# nceubadge.net
KiCad netlist of a schematic drawn in EAGLE
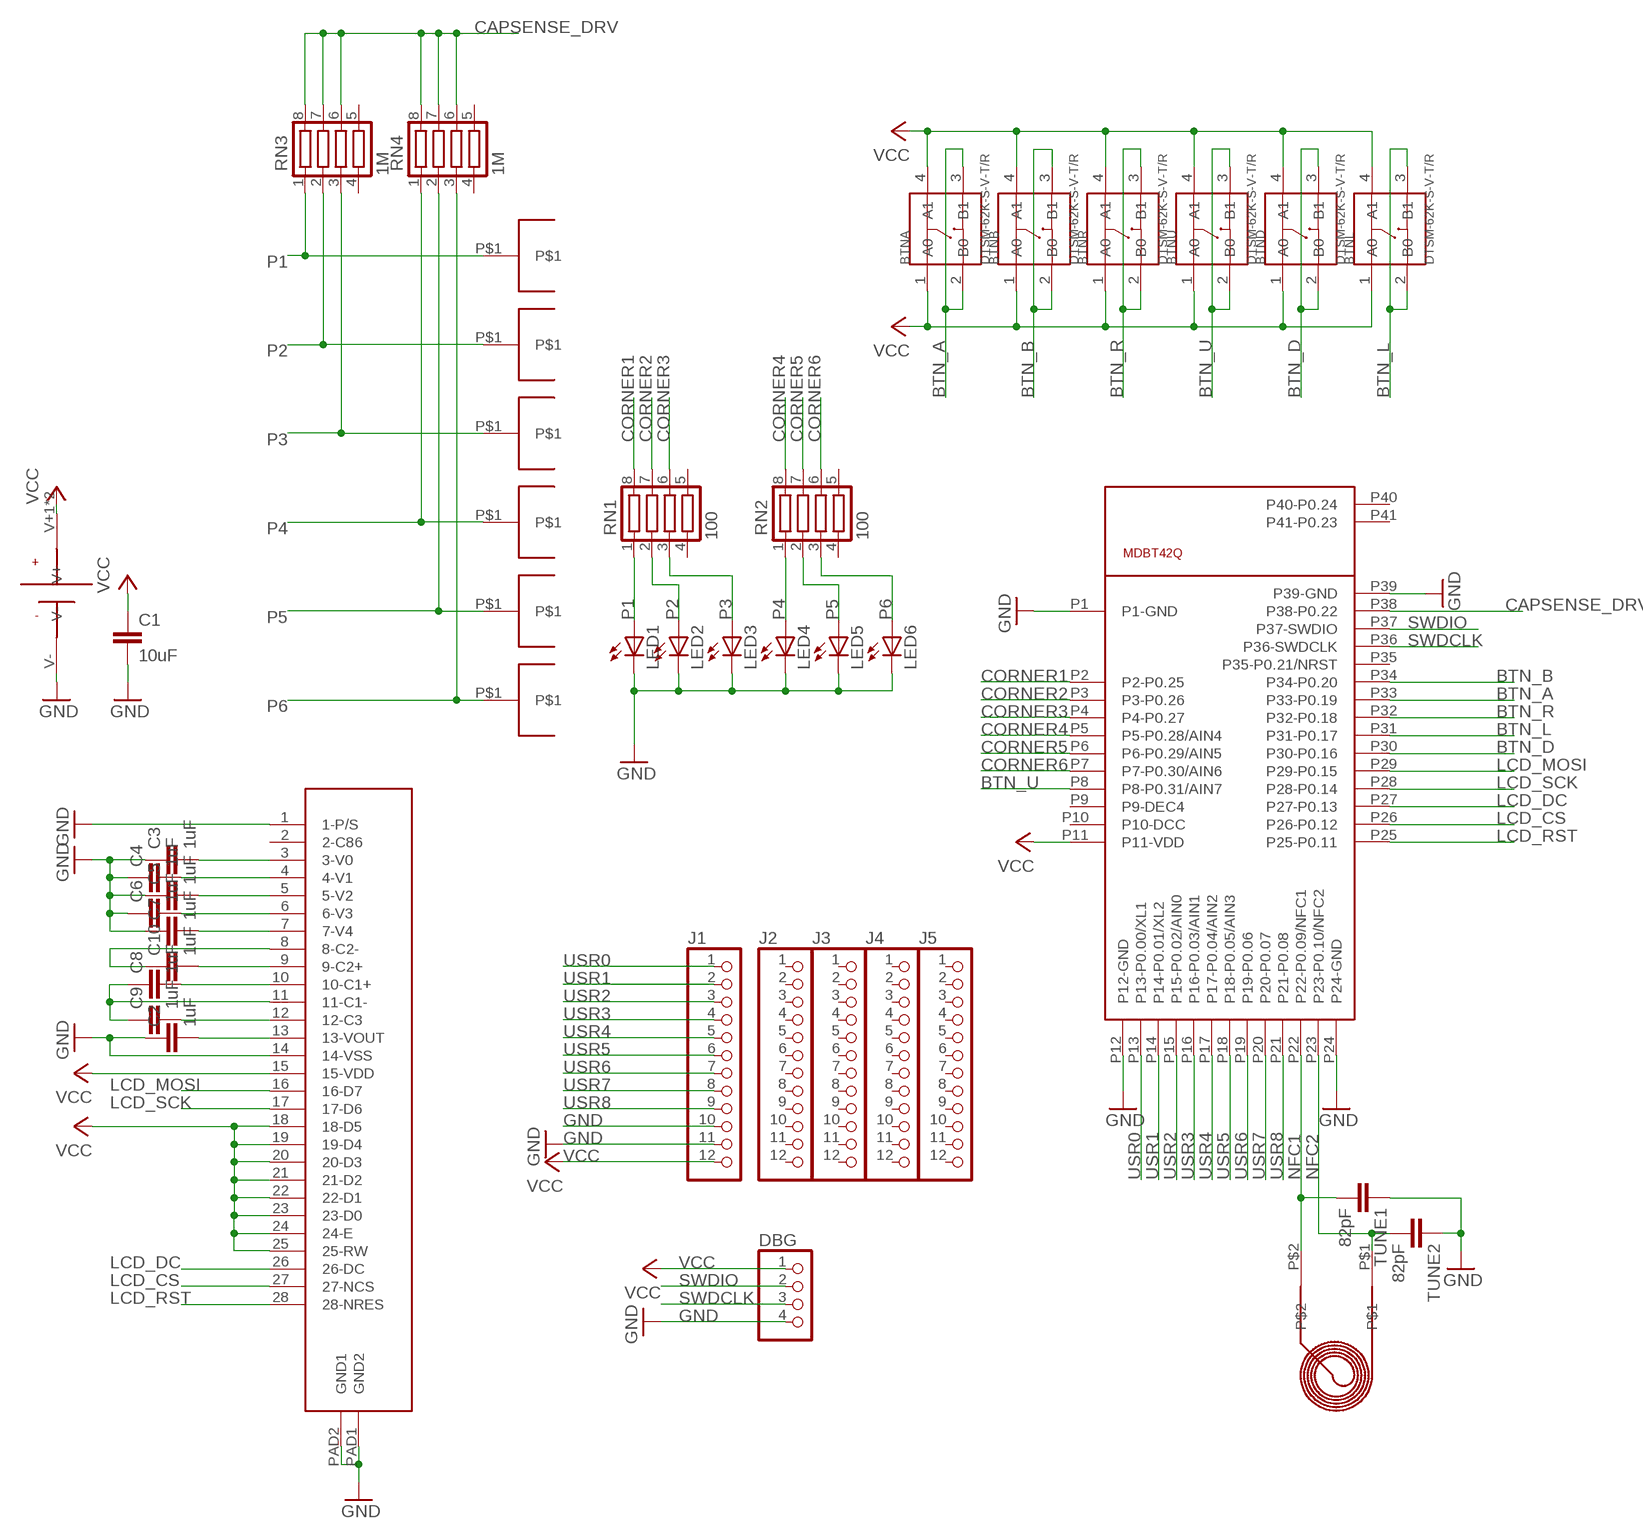
[diagram p0: schematic, sheet 1]

(export (version "E")
  (design (tool "Eeschema 10.0.6"))
  (components
    (comp (ref "BTNA")
      (value "DTSM-62K-S-V-T/R")
      (footprint "eagle-import:SW4-SMD-6.0X6.0X5.0MM")
      (libsource (lib "eagle-import") (part "SMD-SWITCH-TACTILE-SPST-NO(4P-D6.0MM)"))
    )
    (comp (ref "BTNB")
      (value "DTSM-62K-S-V-T/R")
      (footprint "eagle-import:SW4-SMD-6.0X6.0X5.0MM")
      (libsource (lib "eagle-import") (part "SMD-SWITCH-TACTILE-SPST-NO(4P-D6.0MM)"))
    )
    (comp (ref "BTND")
      (value "DTSM-62K-S-V-T/R")
      (footprint "eagle-import:SW4-SMD-6.0X6.0X5.0MM")
      (libsource (lib "eagle-import") (part "SMD-SWITCH-TACTILE-SPST-NO(4P-D6.0MM)"))
    )
    (comp (ref "BTNL")
      (value "DTSM-62K-S-V-T/R")
      (footprint "eagle-import:SW4-SMD-6.0X6.0X5.0MM")
      (libsource (lib "eagle-import") (part "SMD-SWITCH-TACTILE-SPST-NO(4P-D6.0MM)"))
    )
    (comp (ref "BTNR")
      (value "DTSM-62K-S-V-T/R")
      (footprint "eagle-import:SW4-SMD-6.0X6.0X5.0MM")
      (libsource (lib "eagle-import") (part "SMD-SWITCH-TACTILE-SPST-NO(4P-D6.0MM)"))
    )
    (comp (ref "BTNU")
      (value "DTSM-62K-S-V-T/R")
      (footprint "eagle-import:SW4-SMD-6.0X6.0X5.0MM")
      (libsource (lib "eagle-import") (part "SMD-SWITCH-TACTILE-SPST-NO(4P-D6.0MM)"))
    )
    (comp (ref "C1")
      (value "10uF")
      (footprint "eagle-import:C0805K")
      (libsource (lib "eagle-import") (part "C-EUC0805K"))
    )
    (comp (ref "C2")
      (value "1uF")
      (footprint "eagle-import:C0603")
      (libsource (lib "eagle-import") (part "C-EUC0603"))
    )
    (comp (ref "C3")
      (value "1uF")
      (footprint "eagle-import:C0603")
      (libsource (lib "eagle-import") (part "C-EUC0603"))
    )
    (comp (ref "C4")
      (value "1uF")
      (footprint "eagle-import:C0603")
      (libsource (lib "eagle-import") (part "C-EUC0603"))
    )
    (comp (ref "C5")
      (value "1uF")
      (footprint "eagle-import:C0603")
      (libsource (lib "eagle-import") (part "C-EUC0603"))
    )
    (comp (ref "C6")
      (value "1uF")
      (footprint "eagle-import:C0603")
      (libsource (lib "eagle-import") (part "C-EUC0603"))
    )
    (comp (ref "C7")
      (value "1uF")
      (footprint "eagle-import:C0603")
      (libsource (lib "eagle-import") (part "C-EUC0603"))
    )
    (comp (ref "C8")
      (value "1uF")
      (footprint "eagle-import:C0603")
      (libsource (lib "eagle-import") (part "C-EUC0603"))
    )
    (comp (ref "C9")
      (value "1uF")
      (footprint "eagle-import:C0603")
      (libsource (lib "eagle-import") (part "C-EUC0603"))
    )
    (comp (ref "C10")
      (value "1uF")
      (footprint "eagle-import:C0603")
      (libsource (lib "eagle-import") (part "C-EUC0603"))
    )
    (comp (ref "DBG")
      (value "PINHD-1X4")
      (footprint "eagle-import:1X04")
      (libsource (lib "eagle-import") (part "PINHD-1X4"))
    )
    (comp (ref "J1")
      (value "PINHD-1X12_2.54-S")
      (footprint "eagle-import:1X12-S")
      (libsource (lib "eagle-import") (part "PINHD-1X12_2.54-S"))
    )
    (comp (ref "J2")
      (value "PINHD-1X12_2.54-S")
      (footprint "eagle-import:1X12-S")
      (libsource (lib "eagle-import") (part "PINHD-1X12_2.54-S"))
    )
    (comp (ref "J3")
      (value "PINHD-1X12_2.54-S")
      (footprint "eagle-import:1X12-S")
      (libsource (lib "eagle-import") (part "PINHD-1X12_2.54-S"))
    )
    (comp (ref "J4")
      (value "PINHD-1X12_2.54-S")
      (footprint "eagle-import:1X12-S")
      (libsource (lib "eagle-import") (part "PINHD-1X12_2.54-S"))
    )
    (comp (ref "J5")
      (value "PINHD-1X12_2.54-S")
      (footprint "eagle-import:1X12-S")
      (libsource (lib "eagle-import") (part "PINHD-1X12_2.54-S"))
    )
    (comp (ref "J8")
      (value "KEYSTONE-3003")
      (footprint "eagle-import:KEYSTONE-3003")
      (libsource (lib "eagle-import") (part "KEYSTONE-3003"))
    )
    (comp (ref "LCD")
      (value "MCCOG128064B12W")
      (footprint "eagle-import:MCOG128064B12W-SPR")
      (libsource (lib "eagle-import") (part "MCCOG128064B12W"))
    )
    (comp (ref "LED1")
      (value "LED5MM")
      (footprint "eagle-import:LED5MM")
      (libsource (lib "eagle-import") (part "LED5MM"))
    )
    (comp (ref "LED2")
      (value "LED5MM")
      (footprint "eagle-import:LED5MM")
      (libsource (lib "eagle-import") (part "LED5MM"))
    )
    (comp (ref "LED3")
      (value "LED5MM")
      (footprint "eagle-import:LED5MM")
      (libsource (lib "eagle-import") (part "LED5MM"))
    )
    (comp (ref "LED4")
      (value "LED5MM")
      (footprint "eagle-import:LED5MM")
      (libsource (lib "eagle-import") (part "LED5MM"))
    )
    (comp (ref "LED5")
      (value "LED5MM")
      (footprint "eagle-import:LED5MM")
      (libsource (lib "eagle-import") (part "LED5MM"))
    )
    (comp (ref "LED6")
      (value "LED5MM")
      (footprint "eagle-import:LED5MM")
      (libsource (lib "eagle-import") (part "LED5MM"))
    )
    (comp (ref "RN1")
      (value "100")
      (footprint "eagle-import:CTS742C083")
      (libsource (lib "eagle-import") (part "CTS742C083"))
    )
    (comp (ref "RN2")
      (value "100")
      (footprint "eagle-import:CTS742C083")
      (libsource (lib "eagle-import") (part "CTS742C083"))
    )
    (comp (ref "RN3")
      (value "1M")
      (footprint "eagle-import:CTS742C083")
      (libsource (lib "eagle-import") (part "CTS742C083"))
    )
    (comp (ref "RN4")
      (value "1M")
      (footprint "eagle-import:CTS742C083")
      (libsource (lib "eagle-import") (part "CTS742C083"))
    )
    (comp (ref "TUNE1")
      (value "82pF")
      (footprint "eagle-import:C0603")
      (libsource (lib "eagle-import") (part "C-EUC0603"))
    )
    (comp (ref "TUNE2")
      (value "82pF")
      (footprint "eagle-import:C0603")
      (libsource (lib "eagle-import") (part "C-EUC0603"))
    )
    (comp (ref "U$2")
      (value "BANANAPLUG")
      (footprint "eagle-import:BANANAPLUG")
      (libsource (lib "eagle-import") (part "BANANAPLUG"))
    )
    (comp (ref "U$3")
      (value "BANANAPLUG")
      (footprint "eagle-import:BANANAPLUG")
      (libsource (lib "eagle-import") (part "BANANAPLUG"))
    )
    (comp (ref "U$4")
      (value "BANANAPLUG")
      (footprint "eagle-import:BANANAPLUG")
      (libsource (lib "eagle-import") (part "BANANAPLUG"))
    )
    (comp (ref "U$5")
      (value "BANANAPLUG")
      (footprint "eagle-import:BANANAPLUG")
      (libsource (lib "eagle-import") (part "BANANAPLUG"))
    )
    (comp (ref "U$6")
      (value "BANANAPLUG")
      (footprint "eagle-import:BANANAPLUG")
      (libsource (lib "eagle-import") (part "BANANAPLUG"))
    )
    (comp (ref "U$7")
      (value "BANANAPLUG")
      (footprint "eagle-import:BANANAPLUG")
      (libsource (lib "eagle-import") (part "BANANAPLUG"))
    )
    (comp (ref "U$8")
      (value "NFC")
      (footprint "eagle-import:NFC")
      (libsource (lib "eagle-import") (part "NFC"))
    )
    (comp (ref "U1")
      (value "MDBT42Q")
      (footprint "eagle-import:MDBT40")
      (libsource (lib "eagle-import") (part "MDBT42Q"))
    )
  )
  (nets
    (net (code "1") (name "/BTN_A") (class "Default")
      (node (ref "BTNA") (pin "2") (pinfunction "B0_2") (pintype "bidirectional"))
      (node (ref "BTNA") (pin "3") (pinfunction "B1_3") (pintype "bidirectional"))
      (node (ref "U1") (pin "P33") (pinfunction "P33-P0.19_P33") (pintype "bidirectional"))
    )
    (net (code "2") (name "/BTN_B") (class "Default")
      (node (ref "BTNB") (pin "2") (pinfunction "B0_2") (pintype "bidirectional"))
      (node (ref "BTNB") (pin "3") (pinfunction "B1_3") (pintype "bidirectional"))
      (node (ref "U1") (pin "P34") (pinfunction "P34-P0.20_P34") (pintype "bidirectional"))
    )
    (net (code "3") (name "/BTN_D") (class "Default")
      (node (ref "BTND") (pin "2") (pinfunction "B0_2") (pintype "bidirectional"))
      (node (ref "BTND") (pin "3") (pinfunction "B1_3") (pintype "bidirectional"))
      (node (ref "U1") (pin "P30") (pinfunction "P30-P0.16_P30") (pintype "bidirectional"))
    )
    (net (code "4") (name "/BTN_L") (class "Default")
      (node (ref "BTNL") (pin "2") (pinfunction "B0_2") (pintype "bidirectional"))
      (node (ref "BTNL") (pin "3") (pinfunction "B1_3") (pintype "bidirectional"))
      (node (ref "U1") (pin "P31") (pinfunction "P31-P0.17_P31") (pintype "bidirectional"))
    )
    (net (code "5") (name "/BTN_R") (class "Default")
      (node (ref "BTNR") (pin "2") (pinfunction "B0_2") (pintype "bidirectional"))
      (node (ref "BTNR") (pin "3") (pinfunction "B1_3") (pintype "bidirectional"))
      (node (ref "U1") (pin "P32") (pinfunction "P32-P0.18_P32") (pintype "bidirectional"))
    )
    (net (code "6") (name "/BTN_U") (class "Default")
      (node (ref "BTNU") (pin "2") (pinfunction "B0_2") (pintype "bidirectional"))
      (node (ref "BTNU") (pin "3") (pinfunction "B1_3") (pintype "bidirectional"))
      (node (ref "U1") (pin "P8") (pinfunction "P8-P0.31/AIN7_P8") (pintype "bidirectional"))
    )
    (net (code "7") (name "/CAPSENSE_DRV") (class "Default")
      (node (ref "RN3") (pin "6") (pinfunction "6_6") (pintype "passive"))
      (node (ref "RN3") (pin "7") (pinfunction "7_7") (pintype "passive"))
      (node (ref "RN3") (pin "8") (pinfunction "8_8") (pintype "passive"))
      (node (ref "RN4") (pin "6") (pinfunction "6_6") (pintype "passive"))
      (node (ref "RN4") (pin "7") (pinfunction "7_7") (pintype "passive"))
      (node (ref "RN4") (pin "8") (pinfunction "8_8") (pintype "passive"))
      (node (ref "U1") (pin "P38") (pinfunction "P38-P0.22_P38") (pintype "bidirectional"))
    )
    (net (code "8") (name "/CORNER1") (class "Default")
      (node (ref "RN1") (pin "8") (pinfunction "8_8") (pintype "passive"))
      (node (ref "U1") (pin "P2") (pinfunction "P2-P0.25_P2") (pintype "bidirectional"))
    )
    (net (code "9") (name "/CORNER2") (class "Default")
      (node (ref "RN1") (pin "7") (pinfunction "7_7") (pintype "passive"))
      (node (ref "U1") (pin "P3") (pinfunction "P3-P0.26_P3") (pintype "bidirectional"))
    )
    (net (code "10") (name "/CORNER3") (class "Default")
      (node (ref "RN1") (pin "6") (pinfunction "6_6") (pintype "passive"))
      (node (ref "U1") (pin "P4") (pinfunction "P4-P0.27_P4") (pintype "bidirectional"))
    )
    (net (code "11") (name "/CORNER4") (class "Default")
      (node (ref "RN2") (pin "8") (pinfunction "8_8") (pintype "passive"))
      (node (ref "U1") (pin "P5") (pinfunction "P5-P0.28/AIN4_P5") (pintype "bidirectional"))
    )
    (net (code "12") (name "/CORNER5") (class "Default")
      (node (ref "RN2") (pin "7") (pinfunction "7_7") (pintype "passive"))
      (node (ref "U1") (pin "P6") (pinfunction "P6-P0.29/AIN5_P6") (pintype "bidirectional"))
    )
    (net (code "13") (name "/CORNER6") (class "Default")
      (node (ref "RN2") (pin "6") (pinfunction "6_6") (pintype "passive"))
      (node (ref "U1") (pin "P7") (pinfunction "P7-P0.30/AIN6_P7") (pintype "bidirectional"))
    )
    (net (code "14") (name "/LCD_CS") (class "Default")
      (node (ref "LCD") (pin "27") (pinfunction "27-NCS_27") (pintype "bidirectional"))
      (node (ref "U1") (pin "P26") (pinfunction "P26-P0.12_P26") (pintype "bidirectional"))
    )
    (net (code "15") (name "/LCD_DC") (class "Default")
      (node (ref "LCD") (pin "26") (pinfunction "26-DC_26") (pintype "bidirectional"))
      (node (ref "U1") (pin "P27") (pinfunction "P27-P0.13_P27") (pintype "bidirectional"))
    )
    (net (code "16") (name "/LCD_MOSI") (class "Default")
      (node (ref "LCD") (pin "16") (pinfunction "16-D7_16") (pintype "bidirectional"))
      (node (ref "U1") (pin "P29") (pinfunction "P29-P0.15_P29") (pintype "bidirectional"))
    )
    (net (code "17") (name "/LCD_RST") (class "Default")
      (node (ref "LCD") (pin "28") (pinfunction "28-NRES_28") (pintype "bidirectional"))
      (node (ref "U1") (pin "P25") (pinfunction "P25-P0.11_P25") (pintype "bidirectional"))
    )
    (net (code "18") (name "/LCD_SCK") (class "Default")
      (node (ref "LCD") (pin "17") (pinfunction "17-D6_17") (pintype "bidirectional"))
      (node (ref "U1") (pin "P28") (pinfunction "P28-P0.14_P28") (pintype "bidirectional"))
    )
    (net (code "19") (name "/NFC1") (class "Default")
      (node (ref "TUNE1") (pin "2") (pinfunction "2_2") (pintype "passive"))
      (node (ref "U$8") (pin "P$2") (pinfunction "P$2_P$2") (pintype "bidirectional"))
      (node (ref "U1") (pin "P22") (pinfunction "P22-P0.09/NFC1_P22") (pintype "bidirectional"))
    )
    (net (code "20") (name "/NFC2") (class "Default")
      (node (ref "TUNE2") (pin "2") (pinfunction "2_2") (pintype "passive"))
      (node (ref "U$8") (pin "P$1") (pinfunction "P$1_P$1") (pintype "bidirectional"))
      (node (ref "U1") (pin "P23") (pinfunction "P23-P0.10/NFC2_P23") (pintype "bidirectional"))
    )
    (net (code "21") (name "/P1") (class "Default")
      (node (ref "LED1") (pin "A") (pinfunction "A_A") (pintype "passive"))
      (node (ref "RN1") (pin "1") (pinfunction "1_1") (pintype "passive"))
      (node (ref "RN3") (pin "1") (pinfunction "1_1") (pintype "passive"))
      (node (ref "U$6") (pin "P$1") (pinfunction "P$1_P$1") (pintype "bidirectional"))
    )
    (net (code "22") (name "/P2") (class "Default")
      (node (ref "LED2") (pin "A") (pinfunction "A_A") (pintype "passive"))
      (node (ref "RN1") (pin "2") (pinfunction "2_2") (pintype "passive"))
      (node (ref "RN3") (pin "2") (pinfunction "2_2") (pintype "passive"))
      (node (ref "U$7") (pin "P$1") (pinfunction "P$1_P$1") (pintype "bidirectional"))
    )
    (net (code "23") (name "/P3") (class "Default")
      (node (ref "LED3") (pin "A") (pinfunction "A_A") (pintype "passive"))
      (node (ref "RN1") (pin "3") (pinfunction "3_3") (pintype "passive"))
      (node (ref "RN3") (pin "3") (pinfunction "3_3") (pintype "passive"))
      (node (ref "U$5") (pin "P$1") (pinfunction "P$1_P$1") (pintype "bidirectional"))
    )
    (net (code "24") (name "/P4") (class "Default")
      (node (ref "LED4") (pin "A") (pinfunction "A_A") (pintype "passive"))
      (node (ref "RN2") (pin "1") (pinfunction "1_1") (pintype "passive"))
      (node (ref "RN4") (pin "1") (pinfunction "1_1") (pintype "passive"))
      (node (ref "U$4") (pin "P$1") (pinfunction "P$1_P$1") (pintype "bidirectional"))
    )
    (net (code "25") (name "/P5") (class "Default")
      (node (ref "LED5") (pin "A") (pinfunction "A_A") (pintype "passive"))
      (node (ref "RN2") (pin "2") (pinfunction "2_2") (pintype "passive"))
      (node (ref "RN4") (pin "2") (pinfunction "2_2") (pintype "passive"))
      (node (ref "U$3") (pin "P$1") (pinfunction "P$1_P$1") (pintype "bidirectional"))
    )
    (net (code "26") (name "/P6") (class "Default")
      (node (ref "LED6") (pin "A") (pinfunction "A_A") (pintype "passive"))
      (node (ref "RN2") (pin "3") (pinfunction "3_3") (pintype "passive"))
      (node (ref "RN4") (pin "3") (pinfunction "3_3") (pintype "passive"))
      (node (ref "U$2") (pin "P$1") (pinfunction "P$1_P$1") (pintype "bidirectional"))
    )
    (net (code "27") (name "/SWDCLK") (class "Default")
      (node (ref "DBG") (pin "3") (pinfunction "3_3") (pintype "passive"))
      (node (ref "U1") (pin "P36") (pinfunction "P36-SWDCLK_P36") (pintype "bidirectional"))
    )
    (net (code "28") (name "/SWDIO") (class "Default")
      (node (ref "DBG") (pin "2") (pinfunction "2_2") (pintype "passive"))
      (node (ref "U1") (pin "P37") (pinfunction "P37-SWDIO_P37") (pintype "bidirectional"))
    )
    (net (code "29") (name "/USR0") (class "Default")
      (node (ref "J1") (pin "1") (pinfunction "1_1") (pintype "passive"))
      (node (ref "U1") (pin "P13") (pinfunction "P13-P0.00/XL1_P13") (pintype "bidirectional"))
    )
    (net (code "30") (name "/USR1") (class "Default")
      (node (ref "J1") (pin "2") (pinfunction "2_2") (pintype "passive"))
      (node (ref "U1") (pin "P14") (pinfunction "P14-P0.01/XL2_P14") (pintype "bidirectional"))
    )
    (net (code "31") (name "/USR2") (class "Default")
      (node (ref "J1") (pin "3") (pinfunction "3_3") (pintype "passive"))
      (node (ref "U1") (pin "P15") (pinfunction "P15-P0.02/AIN0_P15") (pintype "bidirectional"))
    )
    (net (code "32") (name "/USR3") (class "Default")
      (node (ref "J1") (pin "4") (pinfunction "4_4") (pintype "passive"))
      (node (ref "U1") (pin "P16") (pinfunction "P16-P0.03/AIN1_P16") (pintype "bidirectional"))
    )
    (net (code "33") (name "/USR4") (class "Default")
      (node (ref "J1") (pin "5") (pinfunction "5_5") (pintype "passive"))
      (node (ref "U1") (pin "P17") (pinfunction "P17-P0.04/AIN2_P17") (pintype "bidirectional"))
    )
    (net (code "34") (name "/USR5") (class "Default")
      (node (ref "J1") (pin "6") (pinfunction "6_6") (pintype "passive"))
      (node (ref "U1") (pin "P18") (pinfunction "P18-P0.05/AIN3_P18") (pintype "bidirectional"))
    )
    (net (code "35") (name "/USR6") (class "Default")
      (node (ref "J1") (pin "7") (pinfunction "7_7") (pintype "passive"))
      (node (ref "U1") (pin "P19") (pinfunction "P19-P0.06_P19") (pintype "bidirectional"))
    )
    (net (code "36") (name "/USR7") (class "Default")
      (node (ref "J1") (pin "8") (pinfunction "8_8") (pintype "passive"))
      (node (ref "U1") (pin "P20") (pinfunction "P20-P0.07_P20") (pintype "bidirectional"))
    )
    (net (code "37") (name "/USR8") (class "Default")
      (node (ref "J1") (pin "9") (pinfunction "9_9") (pintype "passive"))
      (node (ref "U1") (pin "P21") (pinfunction "P21-P0.08_P21") (pintype "bidirectional"))
    )
    (net (code "38") (name "GND") (class "Default")
      (node (ref "C1") (pin "2") (pinfunction "2_2") (pintype "passive"))
      (node (ref "C2") (pin "1") (pinfunction "1_1") (pintype "passive"))
      (node (ref "C3") (pin "1") (pinfunction "1_1") (pintype "passive"))
      (node (ref "C4") (pin "1") (pinfunction "1_1") (pintype "passive"))
      (node (ref "C5") (pin "1") (pinfunction "1_1") (pintype "passive"))
      (node (ref "C6") (pin "1") (pinfunction "1_1") (pintype "passive"))
      (node (ref "C7") (pin "1") (pinfunction "1_1") (pintype "passive"))
      (node (ref "DBG") (pin "4") (pinfunction "4_4") (pintype "passive"))
      (node (ref "J1") (pin "10") (pinfunction "10_10") (pintype "passive"))
      (node (ref "J1") (pin "11") (pinfunction "11_11") (pintype "passive"))
      (node (ref "J8") (pin "V-") (pinfunction "V-_V-") (pintype "bidirectional"))
      (node (ref "LCD") (pin "1") (pinfunction "1-P/S_1") (pintype "bidirectional"))
      (node (ref "LCD") (pin "14") (pinfunction "14-VSS_14") (pintype "bidirectional"))
      (node (ref "LCD") (pin "PAD1") (pinfunction "GND2_PAD1") (pintype "bidirectional"))
      (node (ref "LCD") (pin "PAD2") (pinfunction "GND1_PAD2") (pintype "bidirectional"))
      (node (ref "LED1") (pin "K") (pinfunction "C_K") (pintype "passive"))
      (node (ref "LED2") (pin "K") (pinfunction "C_K") (pintype "passive"))
      (node (ref "LED3") (pin "K") (pinfunction "C_K") (pintype "passive"))
      (node (ref "LED4") (pin "K") (pinfunction "C_K") (pintype "passive"))
      (node (ref "LED5") (pin "K") (pinfunction "C_K") (pintype "passive"))
      (node (ref "LED6") (pin "K") (pinfunction "C_K") (pintype "passive"))
      (node (ref "TUNE1") (pin "1") (pinfunction "1_1") (pintype "passive"))
      (node (ref "TUNE2") (pin "1") (pinfunction "1_1") (pintype "passive"))
      (node (ref "U1") (pin "P1") (pinfunction "P1-GND_P1") (pintype "bidirectional"))
      (node (ref "U1") (pin "P12") (pinfunction "P12-GND_P12") (pintype "bidirectional"))
      (node (ref "U1") (pin "P24") (pinfunction "P24-GND_P24") (pintype "bidirectional"))
      (node (ref "U1") (pin "P39") (pinfunction "P39-GND_P39") (pintype "bidirectional"))
    )
    (net (code "39") (name "Net-(LCD-3-V0)") (class "Default")
      (node (ref "C3") (pin "2") (pinfunction "2_2") (pintype "passive"))
      (node (ref "LCD") (pin "3") (pinfunction "3-V0_3") (pintype "bidirectional"))
    )
    (net (code "40") (name "Net-(LCD-4-V1)") (class "Default")
      (node (ref "C4") (pin "2") (pinfunction "2_2") (pintype "passive"))
      (node (ref "LCD") (pin "4") (pinfunction "4-V1_4") (pintype "bidirectional"))
    )
    (net (code "41") (name "Net-(LCD-5-V2)") (class "Default")
      (node (ref "C5") (pin "2") (pinfunction "2_2") (pintype "passive"))
      (node (ref "LCD") (pin "5") (pinfunction "5-V2_5") (pintype "bidirectional"))
    )
    (net (code "42") (name "Net-(LCD-6-V3)") (class "Default")
      (node (ref "C6") (pin "2") (pinfunction "2_2") (pintype "passive"))
      (node (ref "LCD") (pin "6") (pinfunction "6-V3_6") (pintype "bidirectional"))
    )
    (net (code "43") (name "Net-(LCD-7-V4)") (class "Default")
      (node (ref "C7") (pin "2") (pinfunction "2_2") (pintype "passive"))
      (node (ref "LCD") (pin "7") (pinfunction "7-V4_7") (pintype "bidirectional"))
    )
    (net (code "44") (name "Net-(LCD-8-C2-)") (class "Default")
      (node (ref "C10") (pin "1") (pinfunction "1_1") (pintype "passive"))
      (node (ref "LCD") (pin "8") (pinfunction "8-C2-_8") (pintype "bidirectional"))
    )
    (net (code "45") (name "Net-(LCD-9-C2+)") (class "Default")
      (node (ref "C10") (pin "2") (pinfunction "2_2") (pintype "passive"))
      (node (ref "LCD") (pin "9") (pinfunction "9-C2+_9") (pintype "bidirectional"))
    )
    (net (code "46") (name "Net-(LCD-10-C1+)") (class "Default")
      (node (ref "C8") (pin "2") (pinfunction "2_2") (pintype "passive"))
      (node (ref "LCD") (pin "10") (pinfunction "10-C1+_10") (pintype "bidirectional"))
    )
    (net (code "47") (name "Net-(LCD-11-C1-)") (class "Default")
      (node (ref "C8") (pin "1") (pinfunction "1_1") (pintype "passive"))
      (node (ref "C9") (pin "1") (pinfunction "1_1") (pintype "passive"))
      (node (ref "LCD") (pin "11") (pinfunction "11-C1-_11") (pintype "bidirectional"))
    )
    (net (code "48") (name "Net-(LCD-12-C3)") (class "Default")
      (node (ref "C9") (pin "2") (pinfunction "2_2") (pintype "passive"))
      (node (ref "LCD") (pin "12") (pinfunction "12-C3_12") (pintype "bidirectional"))
    )
    (net (code "49") (name "Net-(LCD-13-VOUT)") (class "Default")
      (node (ref "C2") (pin "2") (pinfunction "2_2") (pintype "passive"))
      (node (ref "LCD") (pin "13") (pinfunction "13-VOUT_13") (pintype "bidirectional"))
    )
    (net (code "50") (name "VCC") (class "Default")
      (node (ref "BTNA") (pin "1") (pinfunction "A0_1") (pintype "bidirectional"))
      (node (ref "BTNA") (pin "4") (pinfunction "A1_4") (pintype "bidirectional"))
      (node (ref "BTNB") (pin "1") (pinfunction "A0_1") (pintype "bidirectional"))
      (node (ref "BTNB") (pin "4") (pinfunction "A1_4") (pintype "bidirectional"))
      (node (ref "BTND") (pin "1") (pinfunction "A0_1") (pintype "bidirectional"))
      (node (ref "BTND") (pin "4") (pinfunction "A1_4") (pintype "bidirectional"))
      (node (ref "BTNL") (pin "1") (pinfunction "A0_1") (pintype "bidirectional"))
      (node (ref "BTNL") (pin "4") (pinfunction "A1_4") (pintype "bidirectional"))
      (node (ref "BTNR") (pin "1") (pinfunction "A0_1") (pintype "bidirectional"))
      (node (ref "BTNR") (pin "4") (pinfunction "A1_4") (pintype "bidirectional"))
      (node (ref "BTNU") (pin "1") (pinfunction "A0_1") (pintype "bidirectional"))
      (node (ref "BTNU") (pin "4") (pinfunction "A1_4") (pintype "bidirectional"))
      (node (ref "C1") (pin "1") (pinfunction "1_1") (pintype "passive"))
      (node (ref "DBG") (pin "1") (pinfunction "1_1") (pintype "passive"))
      (node (ref "J1") (pin "12") (pinfunction "12_12") (pintype "passive"))
      (node (ref "J8") (pin "V+1") (pinfunction "V+_V+1") (pintype "bidirectional"))
      (node (ref "J8") (pin "V+2") (pinfunction "V+_V+2") (pintype "bidirectional"))
      (node (ref "LCD") (pin "15") (pinfunction "15-VDD_15") (pintype "bidirectional"))
      (node (ref "LCD") (pin "18") (pinfunction "18-D5_18") (pintype "bidirectional"))
      (node (ref "LCD") (pin "19") (pinfunction "19-D4_19") (pintype "bidirectional"))
      (node (ref "LCD") (pin "20") (pinfunction "20-D3_20") (pintype "bidirectional"))
      (node (ref "LCD") (pin "21") (pinfunction "21-D2_21") (pintype "bidirectional"))
      (node (ref "LCD") (pin "22") (pinfunction "22-D1_22") (pintype "bidirectional"))
      (node (ref "LCD") (pin "23") (pinfunction "23-D0_23") (pintype "bidirectional"))
      (node (ref "LCD") (pin "24") (pinfunction "24-E_24") (pintype "bidirectional"))
      (node (ref "LCD") (pin "25") (pinfunction "25-RW_25") (pintype "bidirectional"))
      (node (ref "U1") (pin "P11") (pinfunction "P11-VDD_P11") (pintype "bidirectional"))
    )
    (net (code "51") (name "unconnected-(J2-Pad1)") (class "Default")
      (node (ref "J2") (pin "1") (pinfunction "1_1") (pintype "passive"))
    )
    (net (code "52") (name "unconnected-(J2-Pad2)") (class "Default")
      (node (ref "J2") (pin "2") (pinfunction "2_2") (pintype "passive"))
    )
    (net (code "53") (name "unconnected-(J2-Pad3)") (class "Default")
      (node (ref "J2") (pin "3") (pinfunction "3_3") (pintype "passive"))
    )
    (net (code "54") (name "unconnected-(J2-Pad4)") (class "Default")
      (node (ref "J2") (pin "4") (pinfunction "4_4") (pintype "passive"))
    )
    (net (code "55") (name "unconnected-(J2-Pad5)") (class "Default")
      (node (ref "J2") (pin "5") (pinfunction "5_5") (pintype "passive"))
    )
    (net (code "56") (name "unconnected-(J2-Pad6)") (class "Default")
      (node (ref "J2") (pin "6") (pinfunction "6_6") (pintype "passive"))
    )
    (net (code "57") (name "unconnected-(J2-Pad7)") (class "Default")
      (node (ref "J2") (pin "7") (pinfunction "7_7") (pintype "passive"))
    )
    (net (code "58") (name "unconnected-(J2-Pad8)") (class "Default")
      (node (ref "J2") (pin "8") (pinfunction "8_8") (pintype "passive"))
    )
    (net (code "59") (name "unconnected-(J2-Pad9)") (class "Default")
      (node (ref "J2") (pin "9") (pinfunction "9_9") (pintype "passive"))
    )
    (net (code "60") (name "unconnected-(J2-Pad10)") (class "Default")
      (node (ref "J2") (pin "10") (pinfunction "10_10") (pintype "passive"))
    )
    (net (code "61") (name "unconnected-(J2-Pad11)") (class "Default")
      (node (ref "J2") (pin "11") (pinfunction "11_11") (pintype "passive"))
    )
    (net (code "62") (name "unconnected-(J2-Pad12)") (class "Default")
      (node (ref "J2") (pin "12") (pinfunction "12_12") (pintype "passive"))
    )
    (net (code "63") (name "unconnected-(J3-Pad1)") (class "Default")
      (node (ref "J3") (pin "1") (pinfunction "1_1") (pintype "passive"))
    )
    (net (code "64") (name "unconnected-(J3-Pad2)") (class "Default")
      (node (ref "J3") (pin "2") (pinfunction "2_2") (pintype "passive"))
    )
    (net (code "65") (name "unconnected-(J3-Pad3)") (class "Default")
      (node (ref "J3") (pin "3") (pinfunction "3_3") (pintype "passive"))
    )
    (net (code "66") (name "unconnected-(J3-Pad4)") (class "Default")
      (node (ref "J3") (pin "4") (pinfunction "4_4") (pintype "passive"))
    )
    (net (code "67") (name "unconnected-(J3-Pad5)") (class "Default")
      (node (ref "J3") (pin "5") (pinfunction "5_5") (pintype "passive"))
    )
    (net (code "68") (name "unconnected-(J3-Pad6)") (class "Default")
      (node (ref "J3") (pin "6") (pinfunction "6_6") (pintype "passive"))
    )
    (net (code "69") (name "unconnected-(J3-Pad7)") (class "Default")
      (node (ref "J3") (pin "7") (pinfunction "7_7") (pintype "passive"))
    )
    (net (code "70") (name "unconnected-(J3-Pad8)") (class "Default")
      (node (ref "J3") (pin "8") (pinfunction "8_8") (pintype "passive"))
    )
    (net (code "71") (name "unconnected-(J3-Pad9)") (class "Default")
      (node (ref "J3") (pin "9") (pinfunction "9_9") (pintype "passive"))
    )
    (net (code "72") (name "unconnected-(J3-Pad10)") (class "Default")
      (node (ref "J3") (pin "10") (pinfunction "10_10") (pintype "passive"))
    )
    (net (code "73") (name "unconnected-(J3-Pad11)") (class "Default")
      (node (ref "J3") (pin "11") (pinfunction "11_11") (pintype "passive"))
    )
    (net (code "74") (name "unconnected-(J3-Pad12)") (class "Default")
      (node (ref "J3") (pin "12") (pinfunction "12_12") (pintype "passive"))
    )
    (net (code "75") (name "unconnected-(J4-Pad1)") (class "Default")
      (node (ref "J4") (pin "1") (pinfunction "1_1") (pintype "passive"))
    )
    (net (code "76") (name "unconnected-(J4-Pad2)") (class "Default")
      (node (ref "J4") (pin "2") (pinfunction "2_2") (pintype "passive"))
    )
    (net (code "77") (name "unconnected-(J4-Pad3)") (class "Default")
      (node (ref "J4") (pin "3") (pinfunction "3_3") (pintype "passive"))
    )
    (net (code "78") (name "unconnected-(J4-Pad4)") (class "Default")
      (node (ref "J4") (pin "4") (pinfunction "4_4") (pintype "passive"))
    )
    (net (code "79") (name "unconnected-(J4-Pad5)") (class "Default")
      (node (ref "J4") (pin "5") (pinfunction "5_5") (pintype "passive"))
    )
    (net (code "80") (name "unconnected-(J4-Pad6)") (class "Default")
      (node (ref "J4") (pin "6") (pinfunction "6_6") (pintype "passive"))
    )
    (net (code "81") (name "unconnected-(J4-Pad7)") (class "Default")
      (node (ref "J4") (pin "7") (pinfunction "7_7") (pintype "passive"))
    )
    (net (code "82") (name "unconnected-(J4-Pad8)") (class "Default")
      (node (ref "J4") (pin "8") (pinfunction "8_8") (pintype "passive"))
    )
    (net (code "83") (name "unconnected-(J4-Pad9)") (class "Default")
      (node (ref "J4") (pin "9") (pinfunction "9_9") (pintype "passive"))
    )
    (net (code "84") (name "unconnected-(J4-Pad10)") (class "Default")
      (node (ref "J4") (pin "10") (pinfunction "10_10") (pintype "passive"))
    )
    (net (code "85") (name "unconnected-(J4-Pad11)") (class "Default")
      (node (ref "J4") (pin "11") (pinfunction "11_11") (pintype "passive"))
    )
    (net (code "86") (name "unconnected-(J4-Pad12)") (class "Default")
      (node (ref "J4") (pin "12") (pinfunction "12_12") (pintype "passive"))
    )
    (net (code "87") (name "unconnected-(J5-Pad1)") (class "Default")
      (node (ref "J5") (pin "1") (pinfunction "1_1") (pintype "passive"))
    )
    (net (code "88") (name "unconnected-(J5-Pad2)") (class "Default")
      (node (ref "J5") (pin "2") (pinfunction "2_2") (pintype "passive"))
    )
    (net (code "89") (name "unconnected-(J5-Pad3)") (class "Default")
      (node (ref "J5") (pin "3") (pinfunction "3_3") (pintype "passive"))
    )
    (net (code "90") (name "unconnected-(J5-Pad4)") (class "Default")
      (node (ref "J5") (pin "4") (pinfunction "4_4") (pintype "passive"))
    )
    (net (code "91") (name "unconnected-(J5-Pad5)") (class "Default")
      (node (ref "J5") (pin "5") (pinfunction "5_5") (pintype "passive"))
    )
    (net (code "92") (name "unconnected-(J5-Pad6)") (class "Default")
      (node (ref "J5") (pin "6") (pinfunction "6_6") (pintype "passive"))
    )
    (net (code "93") (name "unconnected-(J5-Pad7)") (class "Default")
      (node (ref "J5") (pin "7") (pinfunction "7_7") (pintype "passive"))
    )
    (net (code "94") (name "unconnected-(J5-Pad8)") (class "Default")
      (node (ref "J5") (pin "8") (pinfunction "8_8") (pintype "passive"))
    )
    (net (code "95") (name "unconnected-(J5-Pad9)") (class "Default")
      (node (ref "J5") (pin "9") (pinfunction "9_9") (pintype "passive"))
    )
    (net (code "96") (name "unconnected-(J5-Pad10)") (class "Default")
      (node (ref "J5") (pin "10") (pinfunction "10_10") (pintype "passive"))
    )
    (net (code "97") (name "unconnected-(J5-Pad11)") (class "Default")
      (node (ref "J5") (pin "11") (pinfunction "11_11") (pintype "passive"))
    )
    (net (code "98") (name "unconnected-(J5-Pad12)") (class "Default")
      (node (ref "J5") (pin "12") (pinfunction "12_12") (pintype "passive"))
    )
    (net (code "99") (name "unconnected-(LCD-2-C86-Pad2)") (class "Default")
      (node (ref "LCD") (pin "2") (pinfunction "2-C86_2") (pintype "bidirectional"))
    )
    (net (code "100") (name "unconnected-(RN1-Pad4)") (class "Default")
      (node (ref "RN1") (pin "4") (pinfunction "4_4") (pintype "passive"))
    )
    (net (code "101") (name "unconnected-(RN1-Pad5)") (class "Default")
      (node (ref "RN1") (pin "5") (pinfunction "5_5") (pintype "passive"))
    )
    (net (code "102") (name "unconnected-(RN2-Pad4)") (class "Default")
      (node (ref "RN2") (pin "4") (pinfunction "4_4") (pintype "passive"))
    )
    (net (code "103") (name "unconnected-(RN2-Pad5)") (class "Default")
      (node (ref "RN2") (pin "5") (pinfunction "5_5") (pintype "passive"))
    )
    (net (code "104") (name "unconnected-(RN3-Pad4)") (class "Default")
      (node (ref "RN3") (pin "4") (pinfunction "4_4") (pintype "passive"))
    )
    (net (code "105") (name "unconnected-(RN3-Pad5)") (class "Default")
      (node (ref "RN3") (pin "5") (pinfunction "5_5") (pintype "passive"))
    )
    (net (code "106") (name "unconnected-(RN4-Pad4)") (class "Default")
      (node (ref "RN4") (pin "4") (pinfunction "4_4") (pintype "passive"))
    )
    (net (code "107") (name "unconnected-(RN4-Pad5)") (class "Default")
      (node (ref "RN4") (pin "5") (pinfunction "5_5") (pintype "passive"))
    )
    (net (code "108") (name "unconnected-(U1-P9-DEC4-PadP9)") (class "Default")
      (node (ref "U1") (pin "P9") (pinfunction "P9-DEC4_P9") (pintype "bidirectional"))
    )
    (net (code "109") (name "unconnected-(U1-P10-DCC-PadP10)") (class "Default")
      (node (ref "U1") (pin "P10") (pinfunction "P10-DCC_P10") (pintype "bidirectional"))
    )
    (net (code "110") (name "unconnected-(U1-P35-P0.21{slash}NRST-PadP35)") (class "Default")
      (node (ref "U1") (pin "P35") (pinfunction "P35-P0.21/NRST_P35") (pintype "bidirectional"))
    )
    (net (code "111") (name "unconnected-(U1-P40-P0.24-PadP40)") (class "Default")
      (node (ref "U1") (pin "P40") (pinfunction "P40-P0.24_P40") (pintype "bidirectional"))
    )
    (net (code "112") (name "unconnected-(U1-P41-P0.23-PadP41)") (class "Default")
      (node (ref "U1") (pin "P41") (pinfunction "P41-P0.23_P41") (pintype "bidirectional"))
    )
  )
)
